# QCopterMV_CAMSPI_Sch.net
KiCad netlist of a schematic drawn in Altium Designer
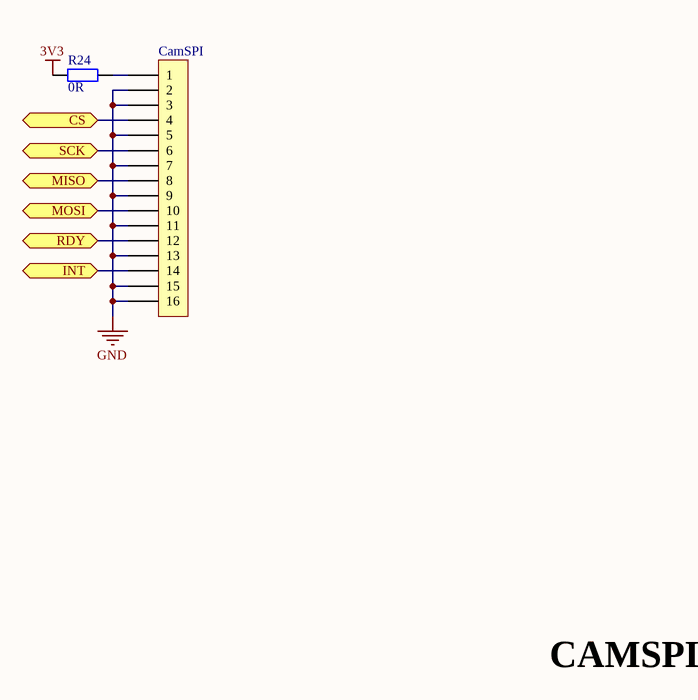
[diagram p0: QCopterMV_CAMSPI_Sch.SchDoc]

(export (version "E")
  (design (tool "Eeschema 10.0.6"))
  (components
    (comp (ref "CamSPI")
      (value "FFC_0.5_16")
      (footprint "PCB_Connector:FFC_0.5_16")
      (description "FFC")
      (libsource (lib "SCH_Connector") (part "FFC_0.5_16"))
    )
    (comp (ref "R24")
      (value "0R")
      (footprint "PCB_Passive:RES_0603")
      (description "Resistor")
      (fields (field (name "Comment") "Res_0603"))
      (libsource (lib "SCH_Passive") (part "Res_0603"))
    )
  )
  (nets
    (net (code "1") (name "/CS") (class "Default")
      (node (ref "CamSPI") (pin "4") (pinfunction "4_4") (pintype "passive"))
    )
    (net (code "2") (name "/INT") (class "Default")
      (node (ref "CamSPI") (pin "14") (pinfunction "14_14") (pintype "passive"))
    )
    (net (code "3") (name "/MISO") (class "Default")
      (node (ref "CamSPI") (pin "8") (pinfunction "8_8") (pintype "passive"))
    )
    (net (code "4") (name "/MOSI") (class "Default")
      (node (ref "CamSPI") (pin "10") (pinfunction "10_10") (pintype "passive"))
    )
    (net (code "5") (name "/RDY") (class "Default")
      (node (ref "CamSPI") (pin "12") (pinfunction "12_12") (pintype "passive"))
    )
    (net (code "6") (name "/SCK") (class "Default")
      (node (ref "CamSPI") (pin "6") (pinfunction "6_6") (pintype "passive"))
    )
    (net (code "7") (name "3V3") (class "Default")
      (node (ref "R24") (pin "1") (pinfunction "1_1") (pintype "passive"))
    )
    (net (code "8") (name "GND") (class "Default")
      (node (ref "CamSPI") (pin "11") (pinfunction "11_11") (pintype "passive"))
      (node (ref "CamSPI") (pin "13") (pinfunction "13_13") (pintype "passive"))
      (node (ref "CamSPI") (pin "15") (pinfunction "15_15") (pintype "passive"))
      (node (ref "CamSPI") (pin "16") (pinfunction "16_16") (pintype "passive"))
      (node (ref "CamSPI") (pin "2") (pinfunction "2_2") (pintype "passive"))
      (node (ref "CamSPI") (pin "3") (pinfunction "3_3") (pintype "passive"))
      (node (ref "CamSPI") (pin "5") (pinfunction "5_5") (pintype "passive"))
      (node (ref "CamSPI") (pin "7") (pinfunction "7_7") (pintype "passive"))
      (node (ref "CamSPI") (pin "9") (pinfunction "9_9") (pintype "passive"))
    )
    (net (code "9") (name "Net-(CamSPI-Pad1)") (class "Default")
      (node (ref "CamSPI") (pin "1") (pinfunction "1_1") (pintype "passive"))
      (node (ref "R24") (pin "2") (pinfunction "2_2") (pintype "passive"))
    )
  )
)
